# 8P8C-to-6P6C.net
KiCad netlist of a schematic drawn in EAGLE
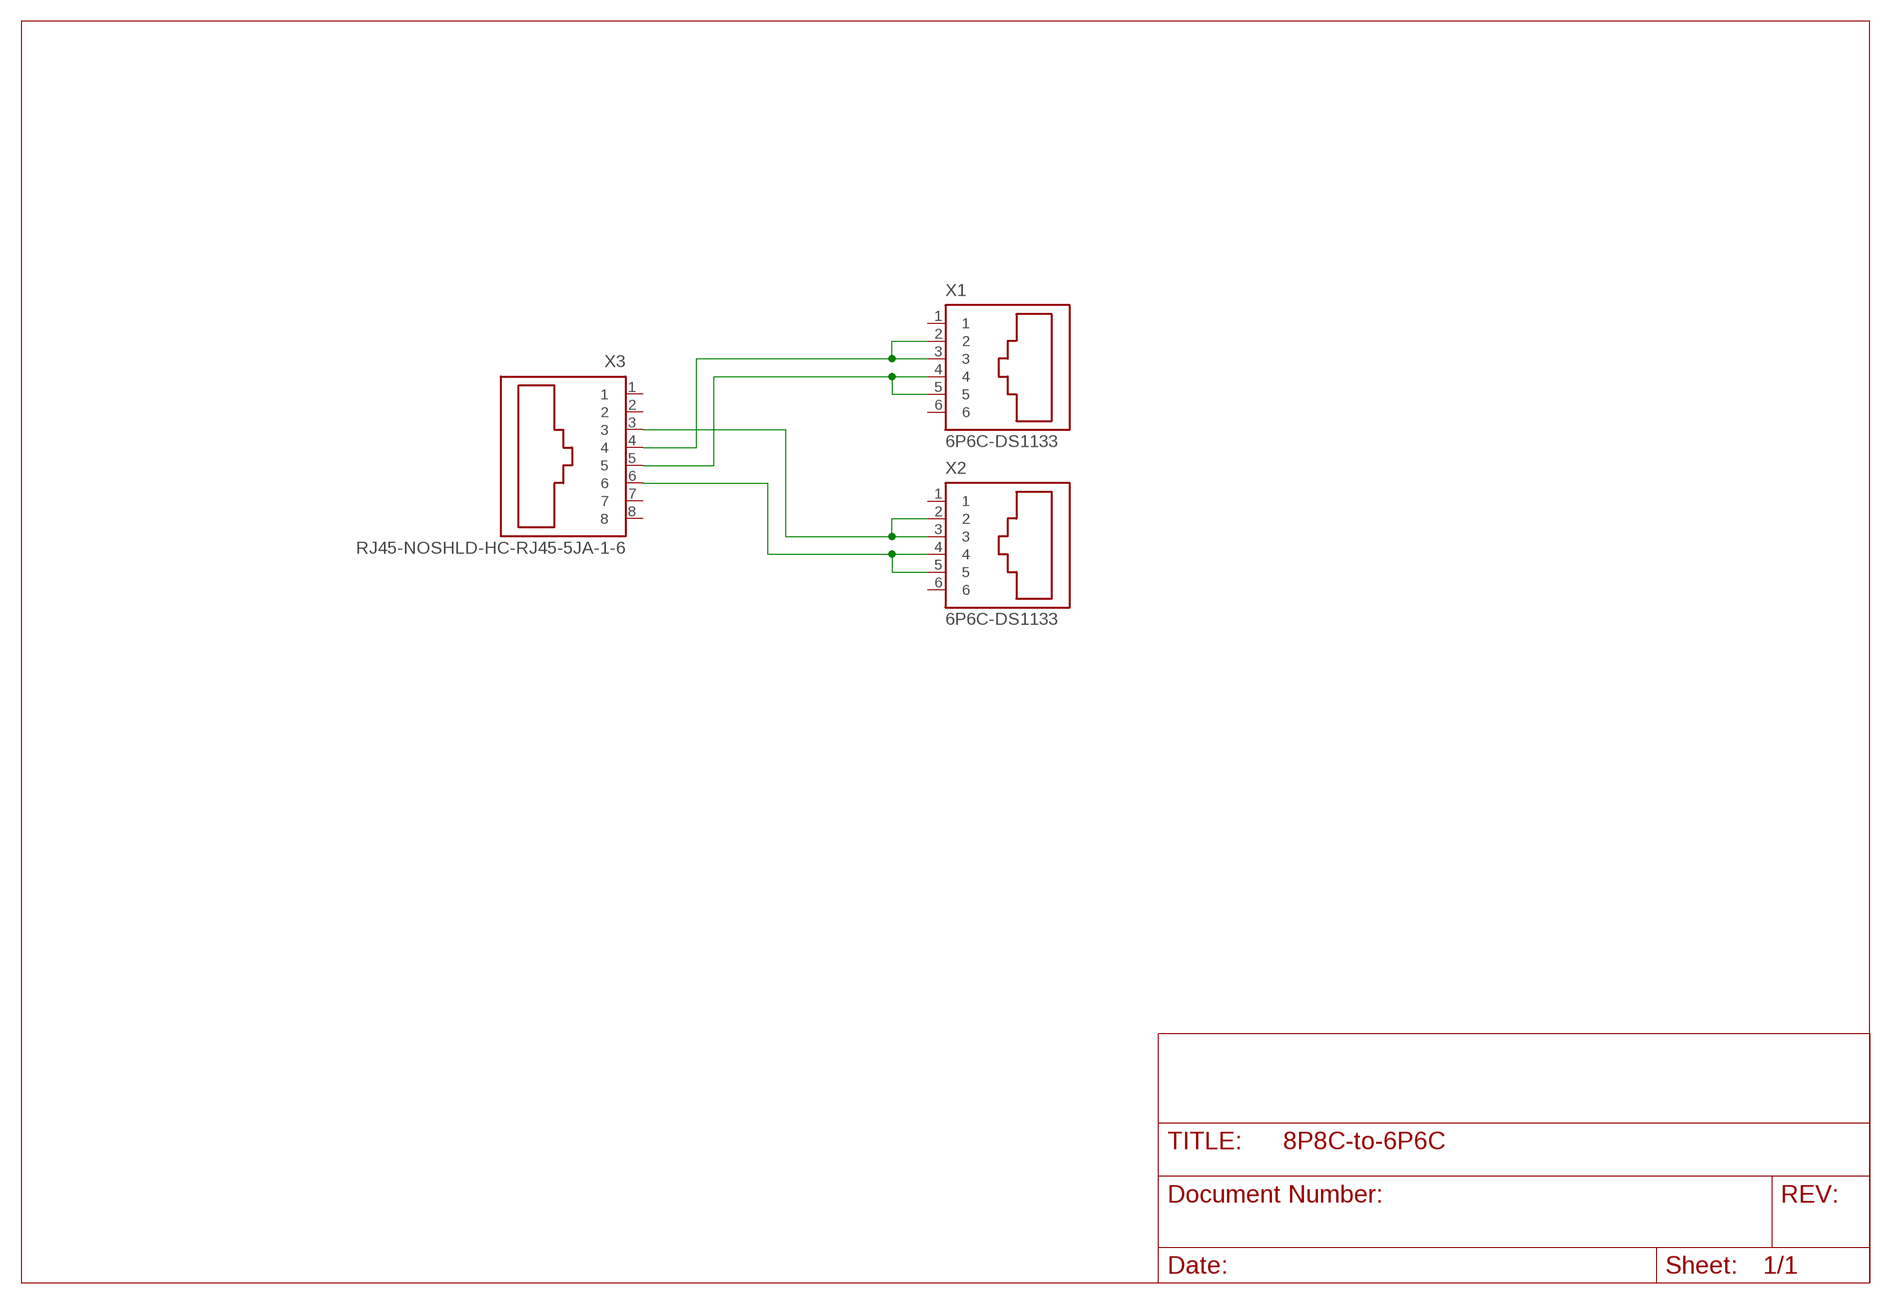
[diagram p0: schematic, sheet 1]

(export (version "E")
  (design (tool "Eeschema 10.0.6"))
  (components
    (comp (ref "X1")
      (value "6P6C-DS1133")
      (footprint "eagle-import:DS1133")
      (libsource (lib "eagle-import") (part "6P6C-DS1133"))
    )
    (comp (ref "X2")
      (value "6P6C-DS1133")
      (footprint "eagle-import:DS1133")
      (libsource (lib "eagle-import") (part "6P6C-DS1133"))
    )
    (comp (ref "X3")
      (value "RJ45-NOSHLD-HC-RJ45-5JA-1-6")
      (footprint "eagle-import:HC-RJ45-5JA-1-6")
      (libsource (lib "eagle-import") (part "RJ45-NOSHLD-HC-RJ45-5JA-1-6"))
    )
  )
  (nets
    (net (code "1") (name "Net-(X1-Pad2)") (class "Default")
      (node (ref "X1") (pin "2") (pinfunction "2_2") (pintype "passive"))
      (node (ref "X1") (pin "3") (pinfunction "3_3") (pintype "passive"))
      (node (ref "X3") (pin "4") (pinfunction "4_4") (pintype "passive"))
    )
    (net (code "2") (name "Net-(X1-Pad4)") (class "Default")
      (node (ref "X1") (pin "4") (pinfunction "4_4") (pintype "passive"))
      (node (ref "X1") (pin "5") (pinfunction "5_5") (pintype "passive"))
      (node (ref "X3") (pin "5") (pinfunction "5_5") (pintype "passive"))
    )
    (net (code "3") (name "Net-(X2-Pad2)") (class "Default")
      (node (ref "X2") (pin "2") (pinfunction "2_2") (pintype "passive"))
      (node (ref "X2") (pin "3") (pinfunction "3_3") (pintype "passive"))
      (node (ref "X3") (pin "3") (pinfunction "3_3") (pintype "passive"))
    )
    (net (code "4") (name "Net-(X2-Pad4)") (class "Default")
      (node (ref "X2") (pin "4") (pinfunction "4_4") (pintype "passive"))
      (node (ref "X2") (pin "5") (pinfunction "5_5") (pintype "passive"))
      (node (ref "X3") (pin "6") (pinfunction "6_6") (pintype "passive"))
    )
    (net (code "5") (name "unconnected-(X1-Pad1)") (class "Default")
      (node (ref "X1") (pin "1") (pinfunction "1_1") (pintype "passive"))
    )
    (net (code "6") (name "unconnected-(X1-Pad6)") (class "Default")
      (node (ref "X1") (pin "6") (pinfunction "6_6") (pintype "passive"))
    )
    (net (code "7") (name "unconnected-(X2-Pad1)") (class "Default")
      (node (ref "X2") (pin "1") (pinfunction "1_1") (pintype "passive"))
    )
    (net (code "8") (name "unconnected-(X2-Pad6)") (class "Default")
      (node (ref "X2") (pin "6") (pinfunction "6_6") (pintype "passive"))
    )
    (net (code "9") (name "unconnected-(X3-Pad1)") (class "Default")
      (node (ref "X3") (pin "1") (pinfunction "1_1") (pintype "passive"))
    )
    (net (code "10") (name "unconnected-(X3-Pad2)") (class "Default")
      (node (ref "X3") (pin "2") (pinfunction "2_2") (pintype "passive"))
    )
    (net (code "11") (name "unconnected-(X3-Pad7)") (class "Default")
      (node (ref "X3") (pin "7") (pinfunction "7_7") (pintype "passive"))
    )
    (net (code "12") (name "unconnected-(X3-Pad8)") (class "Default")
      (node (ref "X3") (pin "8") (pinfunction "8_8") (pintype "passive"))
    )
  )
)
